# controller.net
KiCad netlist of a schematic drawn in EAGLE
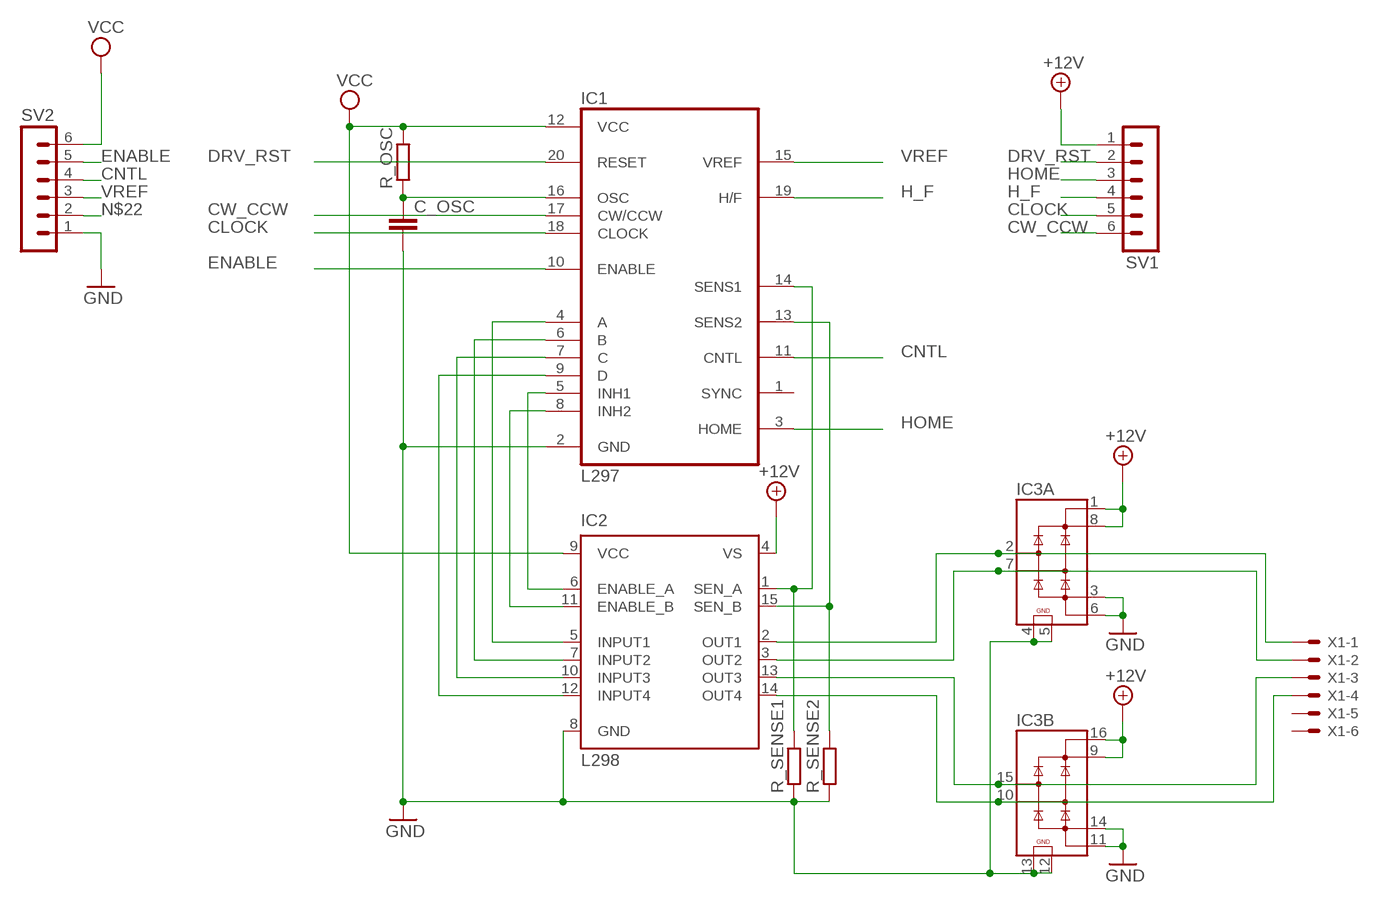
[diagram p0: schematic, sheet 1]

(export (version "E")
  (design (tool "Eeschema 10.0.6"))
  (components
    (comp (ref "C_OSC")
      (value "C-EU025-030X050")
      (footprint "eagle-import:C025-030X050")
      (libsource (lib "eagle-import") (part "C-EU025-030X050"))
    )
    (comp (ref "IC1")
      (value "L297")
      (footprint "eagle-import:DIL20")
      (fields (field (name "MPN") "L297/1"))
      (libsource (lib "eagle-import") (part "L297"))
    )
    (comp (ref "IC2")
      (value "L298")
      (footprint "eagle-import:MULTIWATT-15")
      (fields (field (name "MPN") "L298N"))
      (libsource (lib "eagle-import") (part "L298"))
    )
    (comp (ref "IC3")
      (value "L6210_2")
      (footprint "eagle-import:DIL16")
      (libsource (lib "eagle-import") (part "L6210_2"))
    )
    (comp (ref "R_OSC")
      (value "R-EU_0204/7")
      (footprint "eagle-import:0204_7")
      (libsource (lib "eagle-import") (part "R-EU_0204/7"))
    )
    (comp (ref "R_SENSE1")
      (value "R-EU_0204/7")
      (footprint "eagle-import:0204_7")
      (libsource (lib "eagle-import") (part "R-EU_0204/7"))
    )
    (comp (ref "R_SENSE2")
      (value "R-EU_0204/7")
      (footprint "eagle-import:0204_7")
      (libsource (lib "eagle-import") (part "R-EU_0204/7"))
    )
    (comp (ref "SV1")
      (value "MA06-1")
      (footprint "eagle-import:MA06-1")
      (libsource (lib "eagle-import") (part "MA06-1"))
    )
    (comp (ref "SV2")
      (value "MA06-1")
      (footprint "eagle-import:MA06-1")
      (libsource (lib "eagle-import") (part "MA06-1"))
    )
    (comp (ref "X1")
      (value "22-23-2061")
      (footprint "eagle-import:22-23-2061")
      (fields (field (name "MF") "MOLEX"))
      (libsource (lib "eagle-import") (part "22-23-2061"))
    )
  )
  (nets
    (net (code "1") (name "+12V") (class "Default")
      (node (ref "IC2") (pin "4") (pinfunction "VS_4") (pintype "power_in"))
      (node (ref "IC3") (pin "1") (pinfunction "DC1+_1") (pintype "passive"))
      (node (ref "IC3") (pin "16") (pinfunction "DC1+_16") (pintype "passive"))
      (node (ref "IC3") (pin "8") (pinfunction "DC2+_8") (pintype "passive"))
      (node (ref "IC3") (pin "9") (pinfunction "DC2+_9") (pintype "passive"))
      (node (ref "SV1") (pin "1") (pinfunction "1_1") (pintype "passive"))
    )
    (net (code "2") (name "/CLOCK") (class "Default")
      (node (ref "IC1") (pin "18") (pinfunction "CLOCK_18") (pintype "input"))
      (node (ref "SV1") (pin "5") (pinfunction "5_5") (pintype "passive"))
    )
    (net (code "3") (name "/CNTL") (class "Default")
      (node (ref "IC1") (pin "11") (pinfunction "CNTL_11") (pintype "input"))
      (node (ref "SV2") (pin "4") (pinfunction "4_4") (pintype "passive"))
    )
    (net (code "4") (name "/CW_CCW") (class "Default")
      (node (ref "IC1") (pin "17") (pinfunction "CW/CCW_17") (pintype "input"))
      (node (ref "SV1") (pin "6") (pinfunction "6_6") (pintype "passive"))
    )
    (net (code "5") (name "/DRV_RST") (class "Default")
      (node (ref "IC1") (pin "20") (pinfunction "RESET_20") (pintype "input"))
      (node (ref "SV1") (pin "2") (pinfunction "2_2") (pintype "passive"))
    )
    (net (code "6") (name "/ENABLE") (class "Default")
      (node (ref "IC1") (pin "10") (pinfunction "ENABLE_10") (pintype "input"))
      (node (ref "SV2") (pin "5") (pinfunction "5_5") (pintype "passive"))
    )
    (net (code "7") (name "/HOME") (class "Default")
      (node (ref "IC1") (pin "3") (pinfunction "HOME_3") (pintype "output"))
      (node (ref "SV1") (pin "3") (pinfunction "3_3") (pintype "passive"))
    )
    (net (code "8") (name "/H_F") (class "Default")
      (node (ref "IC1") (pin "19") (pinfunction "H/F_19") (pintype "input"))
      (node (ref "SV1") (pin "4") (pinfunction "4_4") (pintype "passive"))
    )
    (net (code "9") (name "/N$22") (class "Default")
      (node (ref "SV2") (pin "2") (pinfunction "2_2") (pintype "passive"))
    )
    (net (code "10") (name "/VREF") (class "Default")
      (node (ref "IC1") (pin "15") (pinfunction "VREF_15") (pintype "input"))
      (node (ref "SV2") (pin "3") (pinfunction "3_3") (pintype "passive"))
    )
    (net (code "11") (name "GND") (class "Default")
      (node (ref "C_OSC") (pin "2") (pinfunction "2_2") (pintype "passive"))
      (node (ref "IC1") (pin "2") (pinfunction "GND_2") (pintype "power_in"))
      (node (ref "IC2") (pin "8") (pinfunction "GND_8") (pintype "power_in"))
      (node (ref "IC3") (pin "11") (pinfunction "DC2-_11") (pintype "passive"))
      (node (ref "IC3") (pin "12") (pinfunction "GND2_12") (pintype "passive"))
      (node (ref "IC3") (pin "13") (pinfunction "GND1_13") (pintype "passive"))
      (node (ref "IC3") (pin "14") (pinfunction "DC1-_14") (pintype "passive"))
      (node (ref "IC3") (pin "3") (pinfunction "DC1-_3") (pintype "passive"))
      (node (ref "IC3") (pin "4") (pinfunction "GND1_4") (pintype "passive"))
      (node (ref "IC3") (pin "5") (pinfunction "GND2_5") (pintype "passive"))
      (node (ref "IC3") (pin "6") (pinfunction "DC2-_6") (pintype "passive"))
      (node (ref "R_SENSE1") (pin "1") (pinfunction "1_1") (pintype "passive"))
      (node (ref "R_SENSE2") (pin "1") (pinfunction "1_1") (pintype "passive"))
      (node (ref "SV2") (pin "1") (pinfunction "1_1") (pintype "passive"))
    )
    (net (code "12") (name "Net-(IC1-A)") (class "Default")
      (node (ref "IC1") (pin "4") (pinfunction "A_4") (pintype "output"))
      (node (ref "IC2") (pin "5") (pinfunction "INPUT1_5") (pintype "input"))
    )
    (net (code "13") (name "Net-(IC1-B)") (class "Default")
      (node (ref "IC1") (pin "6") (pinfunction "B_6") (pintype "output"))
      (node (ref "IC2") (pin "7") (pinfunction "INPUT2_7") (pintype "input"))
    )
    (net (code "14") (name "Net-(IC1-C)") (class "Default")
      (node (ref "IC1") (pin "7") (pinfunction "C_7") (pintype "output"))
      (node (ref "IC2") (pin "10") (pinfunction "INPUT3_10") (pintype "input"))
    )
    (net (code "15") (name "Net-(IC1-D)") (class "Default")
      (node (ref "IC1") (pin "9") (pinfunction "D_9") (pintype "output"))
      (node (ref "IC2") (pin "12") (pinfunction "INPUT4_12") (pintype "input"))
    )
    (net (code "16") (name "Net-(IC1-INH1)") (class "Default")
      (node (ref "IC1") (pin "5") (pinfunction "INH1_5") (pintype "output"))
      (node (ref "IC2") (pin "6") (pinfunction "ENABLE_A_6") (pintype "input"))
    )
    (net (code "17") (name "Net-(IC1-INH2)") (class "Default")
      (node (ref "IC1") (pin "8") (pinfunction "INH2_8") (pintype "output"))
      (node (ref "IC2") (pin "11") (pinfunction "ENABLE_B_11") (pintype "input"))
    )
    (net (code "18") (name "Net-(IC1-OSC)") (class "Default")
      (node (ref "C_OSC") (pin "1") (pinfunction "1_1") (pintype "passive"))
      (node (ref "IC1") (pin "16") (pinfunction "OSC_16") (pintype "bidirectional"))
      (node (ref "R_OSC") (pin "1") (pinfunction "1_1") (pintype "passive"))
    )
    (net (code "19") (name "Net-(IC1-SENS1)") (class "Default")
      (node (ref "IC1") (pin "14") (pinfunction "SENS1_14") (pintype "output"))
      (node (ref "IC2") (pin "1") (pinfunction "SEN_A_1") (pintype "input"))
      (node (ref "R_SENSE1") (pin "2") (pinfunction "2_2") (pintype "passive"))
    )
    (net (code "20") (name "Net-(IC1-SENS2)") (class "Default")
      (node (ref "IC1") (pin "13") (pinfunction "SENS2_13") (pintype "output"))
      (node (ref "IC2") (pin "15") (pinfunction "SEN_B_15") (pintype "input"))
      (node (ref "R_SENSE2") (pin "2") (pinfunction "2_2") (pintype "passive"))
    )
    (net (code "21") (name "Net-(IC2-OUT1)") (class "Default")
      (node (ref "IC2") (pin "2") (pinfunction "OUT1_2") (pintype "output"))
      (node (ref "IC3") (pin "2") (pinfunction "AC1_2") (pintype "passive"))
      (node (ref "X1") (pin "1") (pinfunction "S_1") (pintype "passive"))
    )
    (net (code "22") (name "Net-(IC2-OUT2)") (class "Default")
      (node (ref "IC2") (pin "3") (pinfunction "OUT2_3") (pintype "output"))
      (node (ref "IC3") (pin "7") (pinfunction "AC2_7") (pintype "passive"))
      (node (ref "X1") (pin "2") (pinfunction "S_2") (pintype "passive"))
    )
    (net (code "23") (name "Net-(IC2-OUT3)") (class "Default")
      (node (ref "IC2") (pin "13") (pinfunction "OUT3_13") (pintype "output"))
      (node (ref "IC3") (pin "15") (pinfunction "AC1_15") (pintype "passive"))
      (node (ref "X1") (pin "3") (pinfunction "S_3") (pintype "passive"))
    )
    (net (code "24") (name "Net-(IC2-OUT4)") (class "Default")
      (node (ref "IC2") (pin "14") (pinfunction "OUT4_14") (pintype "output"))
      (node (ref "IC3") (pin "10") (pinfunction "AC2_10") (pintype "passive"))
      (node (ref "X1") (pin "4") (pinfunction "S_4") (pintype "passive"))
    )
    (net (code "25") (name "VCC") (class "Default")
      (node (ref "IC1") (pin "12") (pinfunction "VCC_12") (pintype "power_in"))
      (node (ref "IC2") (pin "9") (pinfunction "VCC_9") (pintype "power_in"))
      (node (ref "R_OSC") (pin "2") (pinfunction "2_2") (pintype "passive"))
      (node (ref "SV2") (pin "6") (pinfunction "6_6") (pintype "passive"))
    )
    (net (code "26") (name "unconnected-(IC1-SYNC-Pad1)") (class "Default")
      (node (ref "IC1") (pin "1") (pinfunction "SYNC_1") (pintype "output"))
    )
    (net (code "27") (name "unconnected-(X1E-S-Pad5)") (class "Default")
      (node (ref "X1") (pin "5") (pinfunction "S_5") (pintype "passive"))
    )
    (net (code "28") (name "unconnected-(X1F-S-Pad6)") (class "Default")
      (node (ref "X1") (pin "6") (pinfunction "S_6") (pintype "passive"))
    )
  )
)
